# Drivers.net
KiCad netlist of a schematic drawn in Altium Designer
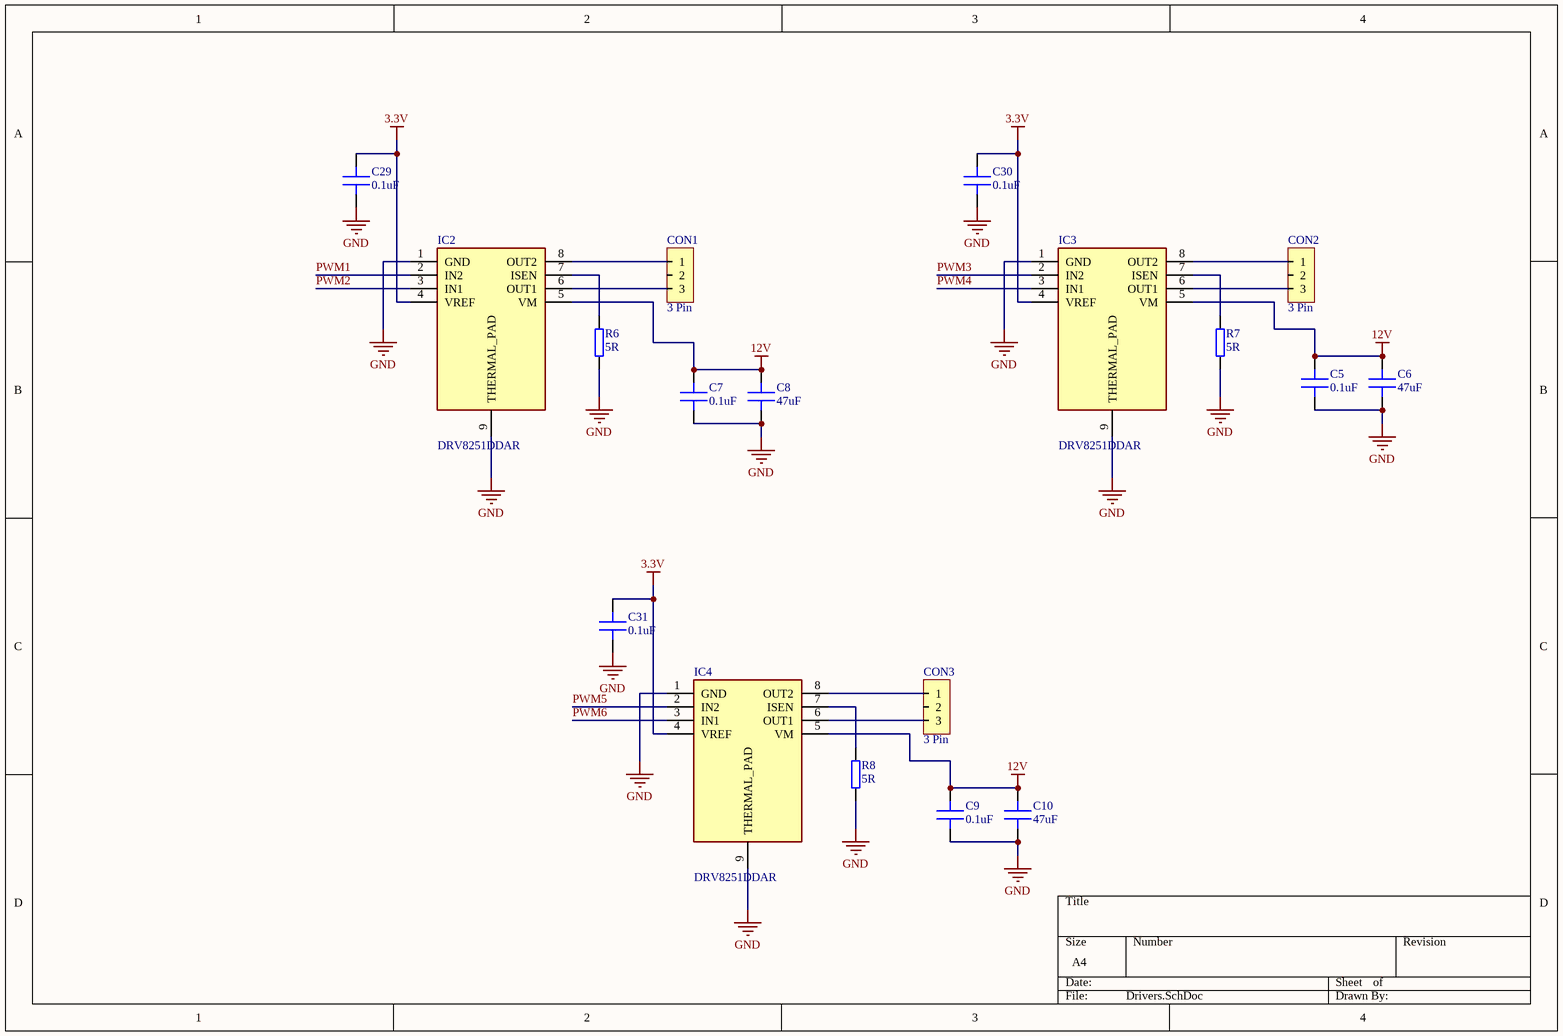
[diagram p0: Drivers.SchDoc]

(export (version "E")
  (design (tool "Eeschema 10.0.6"))
  (components
    (comp (ref "C5")
      (value "0.1uF")
      (footprint "C 0402")
      (description "MLCC Capacitor")
      (libsource (lib "Components") (part "Capacitor"))
    )
    (comp (ref "C6")
      (value "47uF")
      (footprint "C 1206")
      (description "MLCC Capacitor")
      (libsource (lib "Components") (part "Capacitor"))
    )
    (comp (ref "C7")
      (value "0.1uF")
      (footprint "C 0402")
      (description "MLCC Capacitor")
      (libsource (lib "Components") (part "Capacitor"))
    )
    (comp (ref "C8")
      (value "47uF")
      (footprint "C 1206")
      (description "MLCC Capacitor")
      (libsource (lib "Components") (part "Capacitor"))
    )
    (comp (ref "C9")
      (value "0.1uF")
      (footprint "C 0402")
      (description "MLCC Capacitor")
      (libsource (lib "Components") (part "Capacitor"))
    )
    (comp (ref "C10")
      (value "47uF")
      (footprint "C 1206")
      (description "MLCC Capacitor")
      (libsource (lib "Components") (part "Capacitor"))
    )
    (comp (ref "C29")
      (value "0.1uF")
      (footprint "C 0402")
      (description "MLCC Capacitor")
      (libsource (lib "Components") (part "Capacitor"))
    )
    (comp (ref "C30")
      (value "0.1uF")
      (footprint "C 0402")
      (description "MLCC Capacitor")
      (libsource (lib "Components") (part "Capacitor"))
    )
    (comp (ref "C31")
      (value "0.1uF")
      (footprint "C 0402")
      (description "MLCC Capacitor")
      (libsource (lib "Components") (part "Capacitor"))
    )
    (comp (ref "CON1")
      (value "3 Pin")
      (footprint "BM03B-SRSS-TB")
      (libsource (lib "Connectors") (part "3 Pin"))
    )
    (comp (ref "CON2")
      (value "3 Pin")
      (footprint "BM03B-SRSS-TB")
      (libsource (lib "Connectors") (part "3 Pin"))
    )
    (comp (ref "CON3")
      (value "3 Pin")
      (footprint "BM03B-SRSS-TB")
      (libsource (lib "Connectors") (part "3 Pin"))
    )
    (comp (ref "IC2")
      (value "DRV8251DDAR")
      (footprint "SamacSys:SOIC127P600X170-9N")
      (description "Integrated Circuit")
      (fields (field (name "MOUSER PART NUMBER") "595-DRV8251DDAR"))
      (libsource (lib "lf_esp_sch_lib") (part "DRV8251DDAR"))
    )
    (comp (ref "IC3")
      (value "DRV8251DDAR")
      (footprint "SamacSys:SOIC127P600X170-9N")
      (description "Integrated Circuit")
      (fields (field (name "MOUSER PART NUMBER") "595-DRV8251DDAR"))
      (libsource (lib "lf_esp_sch_lib") (part "DRV8251DDAR"))
    )
    (comp (ref "IC4")
      (value "DRV8251DDAR")
      (footprint "SamacSys:SOIC127P600X170-9N")
      (description "Integrated Circuit")
      (fields (field (name "MOUSER PART NUMBER") "595-DRV8251DDAR"))
      (libsource (lib "lf_esp_sch_lib") (part "DRV8251DDAR"))
    )
    (comp (ref "R6")
      (value "5R")
      (footprint "R 1206")
      (description "General pourpouse resistor")
      (libsource (lib "Components") (part "Resistor"))
    )
    (comp (ref "R7")
      (value "5R")
      (footprint "R 1206")
      (description "General pourpouse resistor")
      (libsource (lib "Components") (part "Resistor"))
    )
    (comp (ref "R8")
      (value "5R")
      (footprint "R 1206")
      (description "General pourpouse resistor")
      (libsource (lib "Components") (part "Resistor"))
    )
  )
  (nets
    (net (code "1") (name "/PWM1") (class "Default")
      (node (ref "IC2") (pin "2") (pinfunction "IN2_2") (pintype "passive"))
    )
    (net (code "2") (name "/PWM2") (class "Default")
      (node (ref "IC2") (pin "3") (pinfunction "IN1_3") (pintype "passive"))
    )
    (net (code "3") (name "/PWM3") (class "Default")
      (node (ref "IC3") (pin "2") (pinfunction "IN2_2") (pintype "passive"))
    )
    (net (code "4") (name "/PWM4") (class "Default")
      (node (ref "IC3") (pin "3") (pinfunction "IN1_3") (pintype "passive"))
    )
    (net (code "5") (name "/PWM5") (class "Default")
      (node (ref "IC4") (pin "2") (pinfunction "IN2_2") (pintype "passive"))
    )
    (net (code "6") (name "/PWM6") (class "Default")
      (node (ref "IC4") (pin "3") (pinfunction "IN1_3") (pintype "passive"))
    )
    (net (code "7") (name "3.3V") (class "Default")
      (node (ref "C29") (pin "1") (pinfunction "1_1") (pintype "passive"))
      (node (ref "C30") (pin "1") (pinfunction "1_1") (pintype "passive"))
      (node (ref "C31") (pin "1") (pinfunction "1_1") (pintype "passive"))
      (node (ref "IC2") (pin "4") (pinfunction "VREF_4") (pintype "passive"))
      (node (ref "IC3") (pin "4") (pinfunction "VREF_4") (pintype "passive"))
      (node (ref "IC4") (pin "4") (pinfunction "VREF_4") (pintype "passive"))
    )
    (net (code "8") (name "12V") (class "Default")
      (node (ref "C10") (pin "1") (pinfunction "1_1") (pintype "passive"))
      (node (ref "C5") (pin "1") (pinfunction "1_1") (pintype "passive"))
      (node (ref "C6") (pin "1") (pinfunction "1_1") (pintype "passive"))
      (node (ref "C7") (pin "1") (pinfunction "1_1") (pintype "passive"))
      (node (ref "C8") (pin "1") (pinfunction "1_1") (pintype "passive"))
      (node (ref "C9") (pin "1") (pinfunction "1_1") (pintype "passive"))
      (node (ref "IC2") (pin "5") (pinfunction "VM_5") (pintype "passive"))
      (node (ref "IC3") (pin "5") (pinfunction "VM_5") (pintype "passive"))
      (node (ref "IC4") (pin "5") (pinfunction "VM_5") (pintype "passive"))
    )
    (net (code "9") (name "GND") (class "Default")
      (node (ref "C10") (pin "2") (pinfunction "2_2") (pintype "passive"))
      (node (ref "C29") (pin "2") (pinfunction "2_2") (pintype "passive"))
      (node (ref "C30") (pin "2") (pinfunction "2_2") (pintype "passive"))
      (node (ref "C31") (pin "2") (pinfunction "2_2") (pintype "passive"))
      (node (ref "C5") (pin "2") (pinfunction "2_2") (pintype "passive"))
      (node (ref "C6") (pin "2") (pinfunction "2_2") (pintype "passive"))
      (node (ref "C7") (pin "2") (pinfunction "2_2") (pintype "passive"))
      (node (ref "C8") (pin "2") (pinfunction "2_2") (pintype "passive"))
      (node (ref "C9") (pin "2") (pinfunction "2_2") (pintype "passive"))
      (node (ref "IC2") (pin "1") (pinfunction "GND_1") (pintype "passive"))
      (node (ref "IC2") (pin "9") (pinfunction "THERMAL_PAD_9") (pintype "passive"))
      (node (ref "IC3") (pin "1") (pinfunction "GND_1") (pintype "passive"))
      (node (ref "IC3") (pin "9") (pinfunction "THERMAL_PAD_9") (pintype "passive"))
      (node (ref "IC4") (pin "1") (pinfunction "GND_1") (pintype "passive"))
      (node (ref "IC4") (pin "9") (pinfunction "THERMAL_PAD_9") (pintype "passive"))
      (node (ref "R6") (pin "1") (pinfunction "1_1") (pintype "passive"))
      (node (ref "R7") (pin "1") (pinfunction "1_1") (pintype "passive"))
      (node (ref "R8") (pin "1") (pinfunction "1_1") (pintype "passive"))
    )
    (net (code "10") (name "Net-(IC2-ISEN)") (class "Default")
      (node (ref "IC2") (pin "7") (pinfunction "ISEN_7") (pintype "passive"))
      (node (ref "R6") (pin "2") (pinfunction "2_2") (pintype "passive"))
    )
    (net (code "11") (name "Net-(IC2-OUT1)") (class "Default")
      (node (ref "CON1") (pin "3") (pinfunction "3_3") (pintype "passive"))
      (node (ref "IC2") (pin "6") (pinfunction "OUT1_6") (pintype "passive"))
    )
    (net (code "12") (name "Net-(IC2-OUT2)") (class "Default")
      (node (ref "CON1") (pin "1") (pinfunction "1_1") (pintype "passive"))
      (node (ref "IC2") (pin "8") (pinfunction "OUT2_8") (pintype "passive"))
    )
    (net (code "13") (name "Net-(IC3-ISEN)") (class "Default")
      (node (ref "IC3") (pin "7") (pinfunction "ISEN_7") (pintype "passive"))
      (node (ref "R7") (pin "2") (pinfunction "2_2") (pintype "passive"))
    )
    (net (code "14") (name "Net-(IC3-OUT1)") (class "Default")
      (node (ref "CON2") (pin "3") (pinfunction "3_3") (pintype "passive"))
      (node (ref "IC3") (pin "6") (pinfunction "OUT1_6") (pintype "passive"))
    )
    (net (code "15") (name "Net-(IC3-OUT2)") (class "Default")
      (node (ref "CON2") (pin "1") (pinfunction "1_1") (pintype "passive"))
      (node (ref "IC3") (pin "8") (pinfunction "OUT2_8") (pintype "passive"))
    )
    (net (code "16") (name "Net-(IC4-ISEN)") (class "Default")
      (node (ref "IC4") (pin "7") (pinfunction "ISEN_7") (pintype "passive"))
      (node (ref "R8") (pin "2") (pinfunction "2_2") (pintype "passive"))
    )
    (net (code "17") (name "Net-(IC4-OUT1)") (class "Default")
      (node (ref "CON3") (pin "3") (pinfunction "3_3") (pintype "passive"))
      (node (ref "IC4") (pin "6") (pinfunction "OUT1_6") (pintype "passive"))
    )
    (net (code "18") (name "Net-(IC4-OUT2)") (class "Default")
      (node (ref "CON3") (pin "1") (pinfunction "1_1") (pintype "passive"))
      (node (ref "IC4") (pin "8") (pinfunction "OUT2_8") (pintype "passive"))
    )
    (net (code "19") (name "unconnected-(CON1-Pad2)") (class "Default")
      (node (ref "CON1") (pin "2") (pinfunction "2_2") (pintype "passive"))
    )
    (net (code "20") (name "unconnected-(CON2-Pad2)") (class "Default")
      (node (ref "CON2") (pin "2") (pinfunction "2_2") (pintype "passive"))
    )
    (net (code "21") (name "unconnected-(CON3-Pad2)") (class "Default")
      (node (ref "CON3") (pin "2") (pinfunction "2_2") (pintype "passive"))
    )
  )
)
